# ir.net
KiCad netlist of a schematic drawn in Altium Designer
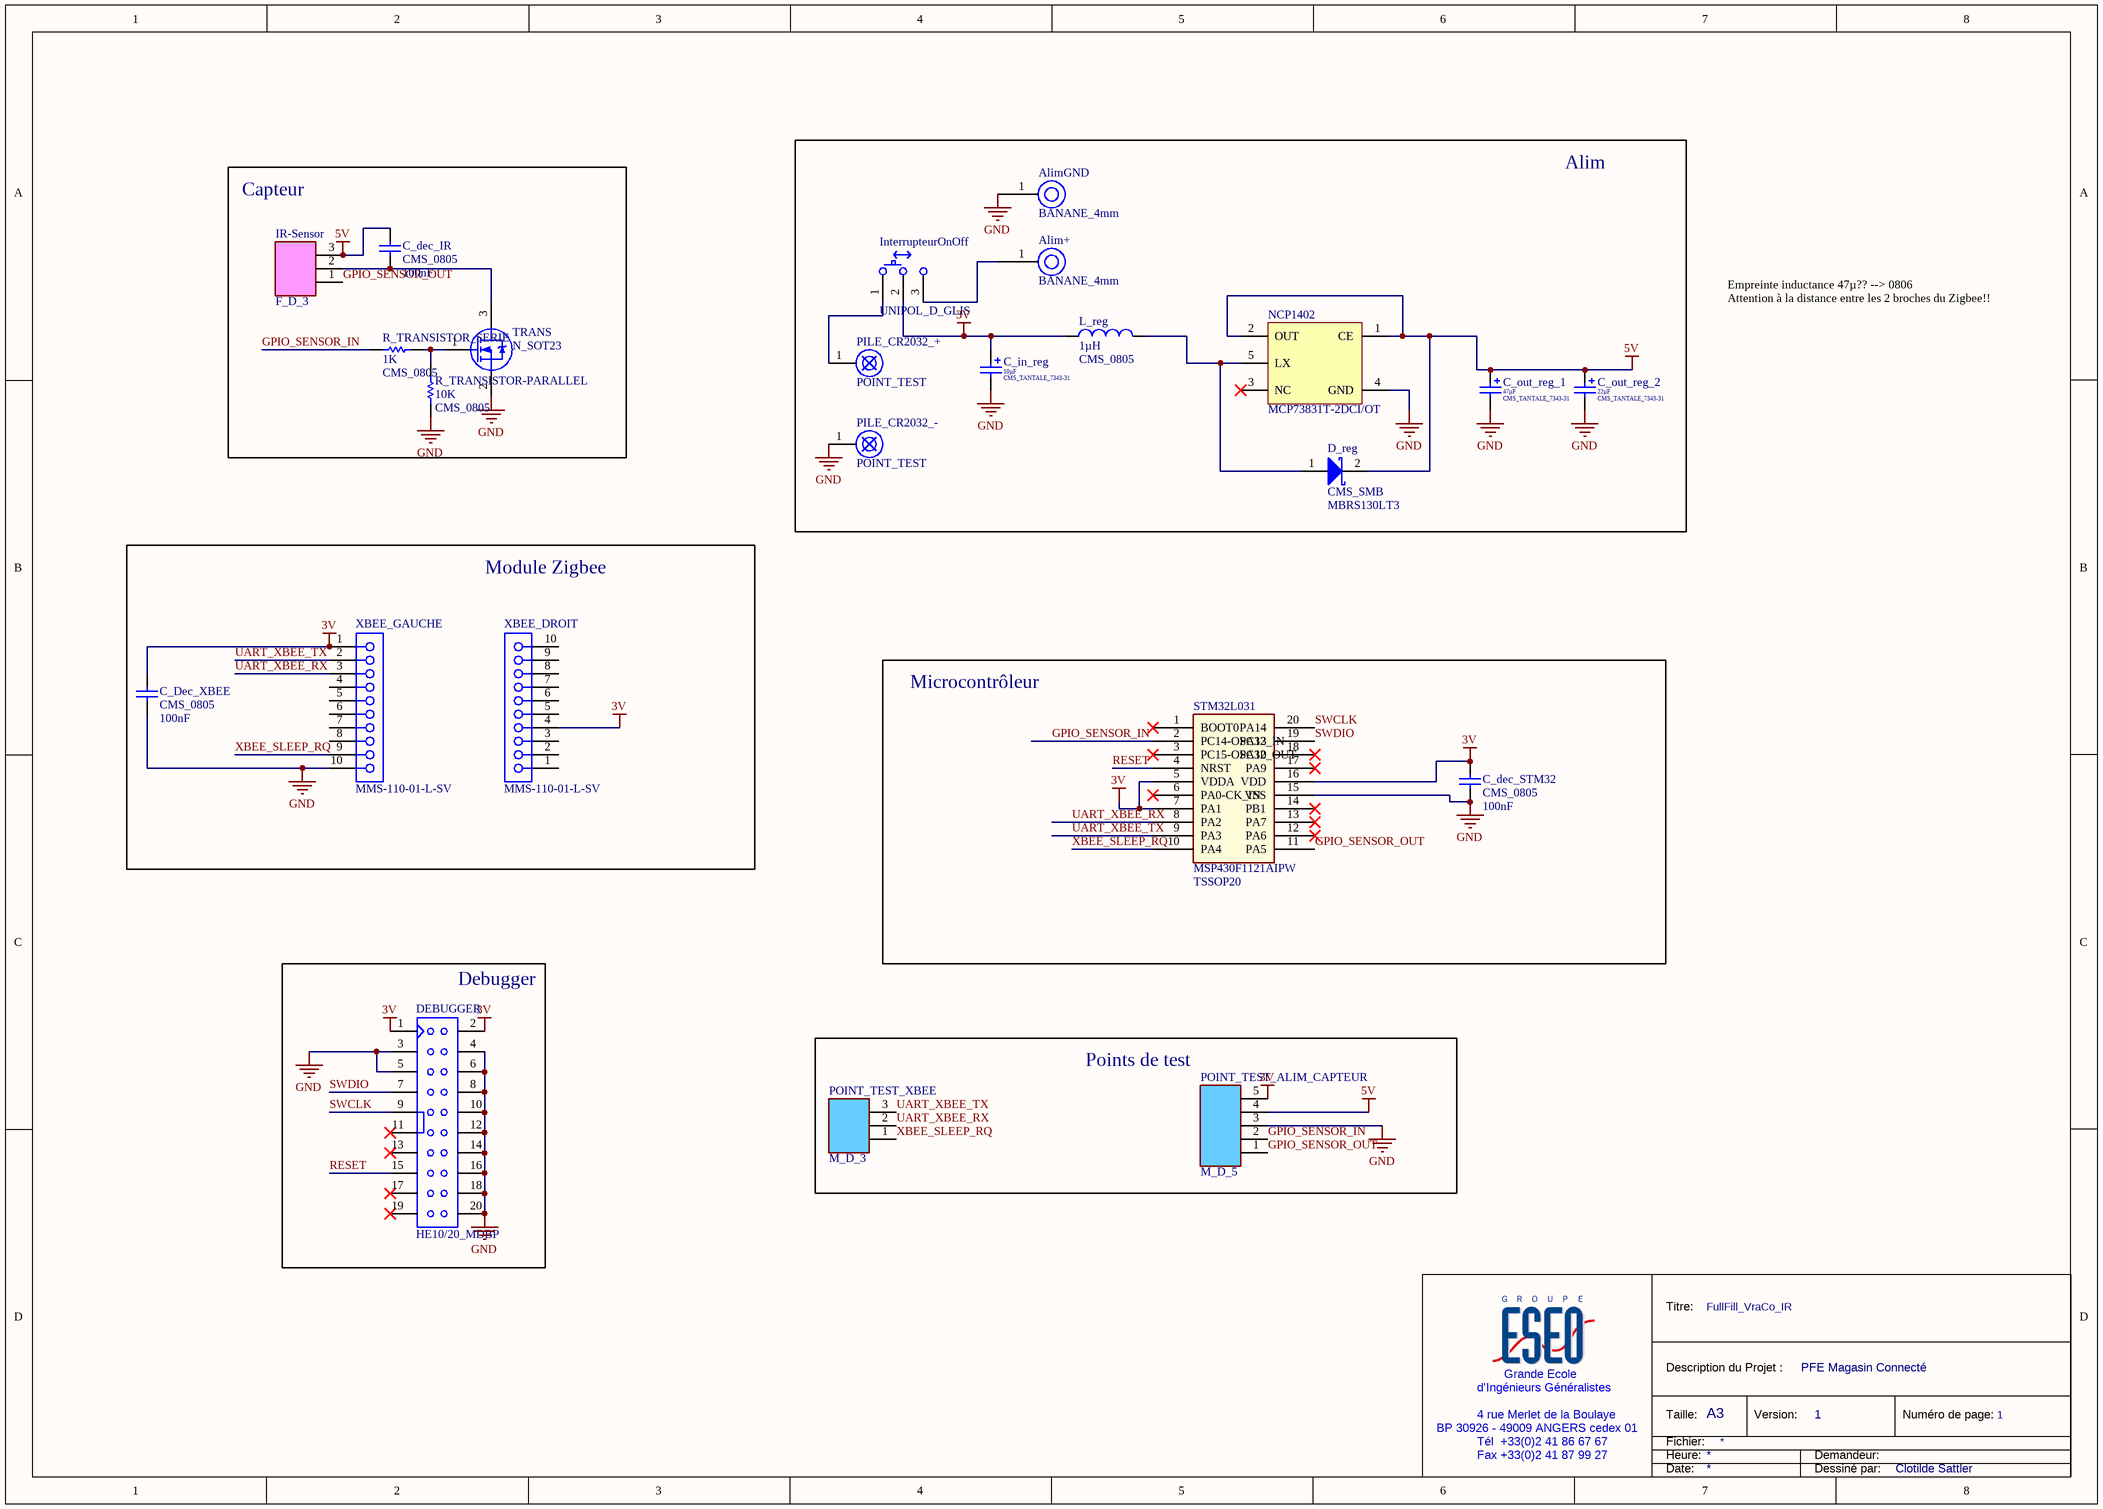
[diagram p0: ir.SchDoc]

(export (version "E")
  (design (tool "Eeschema 10.0.6"))
  (components
    (comp (ref "Alim+")
      (value "DOUILLE BANANE 4mm")
      (footprint "DOUILLE_BANANE_4mm")
      (description "DOUILLE BANANE 4 mm")
      (fields (field (name "TYPE") "BANANE_4mm"))
      (libsource (lib "connecteurs") (part "DOUILLE_BANANE_4mm"))
    )
    (comp (ref "AlimGND")
      (value "DOUILLE BANANE 4mm")
      (footprint "DOUILLE_BANANE_4mm")
      (description "DOUILLE BANANE 4 mm")
      (fields (field (name "TYPE") "BANANE_4mm"))
      (libsource (lib "connecteurs") (part "DOUILLE_BANANE_4mm"))
    )
    (comp (ref "C_dec_IR")
      (value "100nF")
      (footprint "CONDENSATEUR_CMS_0805")
      (description "CONDENSATEUR CMS CERAMIQUE 0805")
      (fields (field (name "TYPE") "CMS_0805") (field (name "Comment") "CMS_0805"))
      (libsource (lib "composants passifs") (part "CONDENSATEUR_CMS_CER_0805"))
    )
    (comp (ref "C_dec_STM32")
      (value "100nF")
      (footprint "CONDENSATEUR_CMS_0805")
      (description "CONDENSATEUR CMS CERAMIQUE 0805")
      (fields (field (name "TYPE") "CMS_0805") (field (name "Comment") "CMS_0805"))
      (libsource (lib "composants passifs") (part "CONDENSATEUR_CMS_CER_0805"))
    )
    (comp (ref "C_Dec_XBEE")
      (value "100nF")
      (footprint "CONDENSATEUR_CMS_0805")
      (description "CONDENSATEUR CMS CERAMIQUE 0805")
      (fields (field (name "TYPE") "CMS_0805") (field (name "Comment") "CMS_0805"))
      (libsource (lib "composants passifs") (part "CONDENSATEUR_CMS_CER_0805"))
    )
    (comp (ref "C_in_reg")
      (value "10µF")
      (footprint "CONDENSATEUR_CMS_POLARISE_TANTALE_D/7343-31")
      (description "CONDENSATEUR CMS POLARISE TANTALE BOITIER D/7343-31")
      (fields
        (field (name "TYPE") "CMS_TANTALE_7343-31")
        (field (name "Comment") "CMS_POLARISE_TANTALE_7343-31")
      )
      (libsource (lib "composants passifs") (part "CONDENSATEUR_CMS_POL_TANT_D_7343-31"))
    )
    (comp (ref "C_out_reg_1")
      (value "47µF")
      (footprint "CONDENSATEUR_CMS_POLARISE_TANTALE_D/7343-31")
      (description "CONDENSATEUR CMS POLARISE TANTALE BOITIER D/7343-31")
      (fields
        (field (name "TYPE") "CMS_TANTALE_7343-31")
        (field (name "Comment") "CMS_POLARISE_TANTALE_7343-31")
      )
      (libsource (lib "composants passifs") (part "CONDENSATEUR_CMS_POL_TANT_D_7343-31"))
    )
    (comp (ref "C_out_reg_2")
      (value "22µF")
      (footprint "CONDENSATEUR_CMS_POLARISE_TANTALE_D/7343-31")
      (description "CONDENSATEUR CMS POLARISE TANTALE BOITIER D/7343-31")
      (fields
        (field (name "TYPE") "CMS_TANTALE_7343-31")
        (field (name "Comment") "CMS_POLARISE_TANTALE_7343-31")
      )
      (libsource (lib "composants passifs") (part "CONDENSATEUR_CMS_POL_TANT_D_7343-31"))
    )
    (comp (ref "DEBUGGER")
      (value "HE10/20_MALE_DROIT_BAS_PROFIL")
      (footprint "HE10/20_M_D_BP")
      (description "EMBASE HE10/20 MALE DROIT BAS PROFIL")
      (fields (field (name "TYPE") "HE10/20_MDBP"))
      (libsource (lib "connecteurs") (part "HE10/20_MALE_DROIT_BAS_PROFIL"))
    )
    (comp (ref "D_reg")
      (value "DIODE_CMS_SCHOTTKY_SMB : MBRS130LT3")
      (footprint "DIODE_CMS_SMB")
      (description "DIODE CMS SCHOTTKY SMB : MBRS130LT3")
      (fields (field (name "PACKAGE") "CMS_SMB") (field (name "TYPE") "MBRS130LT3"))
      (libsource (lib "composants actifs") (part "DIODE_CMS_SCHOTTKY_SMB {colon} MBRS130LT3"))
    )
    (comp (ref "InterrupteurOnOff")
      (value "INTERRUPTEUR_UNIPOLAIRE_DROIT_GLISSIERE")
      (footprint "INTER_UNIPOL_DROIT_GLISS")
      (description "INTERRUPTEUR UNIPOLAIRE DROIT A GLISSIERE")
      (fields (field (name "TYPE") "UNIPOL_D_GLIS"))
      (libsource (lib "commutation") (part "INTERRUPTEUR_UNIPOLAIRE_DROIT_GLISSIERE"))
    )
    (comp (ref "IR-Sensor")
      (value "BARRETTE 3 CONTACTS 1 RANGEE FEMELLE DROITE")
      (footprint "BARRETTE_3_F_D")
      (fields (field (name "TYPE") "F_D_3"))
      (libsource (lib "connecteurs") (part "BARRETTE_3 CONTACTS_1 RANGEE_FEMELLE_DROITE"))
    )
    (comp (ref "L_reg")
      (value "1µH")
      (footprint "INDUCTANCE_CMS_0805")
      (description "INDUCTANCE CMS 0805")
      (fields (field (name "TYPE") "CMS_0805") (field (name "Comment") "INDUCTANCE_CMS_0805"))
      (libsource (lib "composants passifs") (part "INDUCTANCE_CMS_0805"))
    )
    (comp (ref "NCP1402")
      (value "MCP73831T-2DCI/OT")
      (footprint "SOT-23-OT5_N")
      (fields (field (name "MANUFACTURER") "Microchip"))
      (libsource (lib "energie") (part "MCP73831T-2DCI/OT"))
    )
    (comp (ref "PILE_CR2032_+")
      (value "POINT_TEST")
      (footprint "POINT_TEST")
      (description "POINT TEST")
      (libsource (lib "connecteurs") (part "POINT_TEST"))
    )
    (comp (ref "PILE_CR2032_-")
      (value "POINT_TEST")
      (footprint "POINT_TEST")
      (description "POINT TEST")
      (libsource (lib "connecteurs") (part "POINT_TEST"))
    )
    (comp (ref "POINT_TEST_ALIM_CAPTEUR")
      (value "BARRETTE_5 CONTACTS_1 RANGEE_MALE_DROITE")
      (footprint "BARRETTE_5_M_D")
      (description "BARRETTE 5 CONTACTS 1 RANGEE MALE DROITE")
      (fields (field (name "TYPE") "M_D_5"))
      (libsource (lib "connecteurs") (part "BARRETTE_5 CONTACTS_1 RANGEE_MALE_DROITE"))
    )
    (comp (ref "POINT_TEST_XBEE")
      (value "BARRETTE 3 CONTACTS 1 RANGEE MALE DROITE")
      (footprint "BARRETTE_3_M_D")
      (fields (field (name "TYPE") "M_D_3"))
      (libsource (lib "connecteurs") (part "BARRETTE_3 CONTACTS_1 RANGEE_MALE_DROITE"))
    )
    (comp (ref "R_TRANSISTOR-PARALLEL")
      (value "10K")
      (footprint "RESISTANCE_CMS_0805")
      (description "RESISTANCE CMS 0805")
      (fields (field (name "TYPE") "CMS_0805") (field (name "Comment") "RESISTANCE_CMS_0805"))
      (libsource (lib "composants passifs") (part "RESISTANCE_CMS_0805"))
    )
    (comp (ref "R_TRANSISTOR_SERIE")
      (value "1K")
      (footprint "RESISTANCE_CMS_0805")
      (description "RESISTANCE CMS 0805")
      (fields (field (name "TYPE") "CMS_0805") (field (name "Comment") "RESISTANCE_CMS_0805"))
      (libsource (lib "composants passifs") (part "RESISTANCE_CMS_0805"))
    )
    (comp (ref "STM32L031")
      (value "MSP430F1121AIPW_TSSOP20")
      (footprint "TSSOP20_PAS=0.65_LARG=6.4_LONG=6.5")
      (description "MICROCONTROLEUR FLASH - 16BITS - TSSOP20")
      (fields (field (name "TYPE") "MSP430F1121AIPW") (field (name "PACKAGE") "TSSOP20"))
      (libsource (lib "circuits integres") (part "MSP430F1121AIPW_TSSOP20"))
    )
    (comp (ref "TRANS")
      (value "TRANSISTOR_MOSFET-N_SOT23_GSD")
      (footprint "TRANSISTOR_MOSFET-N_SOT23_GSD")
      (description "TRANSISTOR MOSFET CANAL N BOITIER SOT23_GSD")
      (fields (field (name "PACKAGE") "N_SOT23"))
      (libsource (lib "composants actifs") (part "TRANSISTOR_MOSFET-N_SOT23_GSD"))
    )
    (comp (ref "XBEE_DROIT")
      (value "MMS-110-01-L-SV")
      (footprint "SMTC-MMS-110-01-X-SV")
      (fields (field (name "MANUFACTURER") "Samtec"))
      (libsource (lib "Samtec_2_mm_Pitch_Socket_Strips") (part "MMS-110-01-L-SV"))
    )
    (comp (ref "XBEE_GAUCHE")
      (value "MMS-110-01-L-SV")
      (footprint "SMTC-MMS-110-01-X-SV")
      (fields (field (name "MANUFACTURER") "Samtec"))
      (libsource (lib "Samtec_2_mm_Pitch_Socket_Strips") (part "MMS-110-01-L-SV"))
    )
  )
  (nets
    (net (code "1") (name "/GPIO_SENSOR_IN") (class "Default")
      (node (ref "POINT_TEST_ALIM_CAPTEUR") (pin "2") (pinfunction "2_2") (pintype "passive"))
      (node (ref "R_TRANSISTOR_SERIE") (pin "1") (pinfunction "1_1") (pintype "passive"))
      (node (ref "STM32L031") (pin "2") (pinfunction "PC14-OSC32_IN_2") (pintype "passive"))
    )
    (net (code "2") (name "/GPIO_SENSOR_OUT") (class "Default")
      (node (ref "IR-Sensor") (pin "1") (pinfunction "GND_1") (pintype "passive"))
      (node (ref "POINT_TEST_ALIM_CAPTEUR") (pin "1") (pinfunction "1_1") (pintype "passive"))
      (node (ref "STM32L031") (pin "11") (pinfunction "PA5_11") (pintype "passive"))
    )
    (net (code "3") (name "/RESET") (class "Default")
      (node (ref "DEBUGGER") (pin "15") (pinfunction "15_15") (pintype "passive"))
      (node (ref "STM32L031") (pin "4") (pinfunction "NRST_4") (pintype "passive"))
    )
    (net (code "4") (name "/SWCLK") (class "Default")
      (node (ref "DEBUGGER") (pin "9") (pinfunction "9_9") (pintype "passive"))
      (node (ref "STM32L031") (pin "20") (pinfunction "PA14_20") (pintype "passive"))
    )
    (net (code "5") (name "/SWDIO") (class "Default")
      (node (ref "DEBUGGER") (pin "7") (pinfunction "7_7") (pintype "passive"))
      (node (ref "STM32L031") (pin "19") (pinfunction "PA13_19") (pintype "passive"))
    )
    (net (code "6") (name "/UART_XBEE_RX") (class "Default")
      (node (ref "POINT_TEST_XBEE") (pin "2") (pinfunction "2_2") (pintype "passive"))
      (node (ref "STM32L031") (pin "8") (pinfunction "PA2_8") (pintype "passive"))
      (node (ref "XBEE_GAUCHE") (pin "3") (pinfunction "3_3") (pintype "passive"))
    )
    (net (code "7") (name "/UART_XBEE_TX") (class "Default")
      (node (ref "POINT_TEST_XBEE") (pin "3") (pinfunction "3_3") (pintype "passive"))
      (node (ref "STM32L031") (pin "9") (pinfunction "PA3_9") (pintype "passive"))
      (node (ref "XBEE_GAUCHE") (pin "2") (pinfunction "2_2") (pintype "passive"))
    )
    (net (code "8") (name "/XBEE_SLEEP_RQ") (class "Default")
      (node (ref "POINT_TEST_XBEE") (pin "1") (pinfunction "1_1") (pintype "passive"))
      (node (ref "STM32L031") (pin "10") (pinfunction "PA4_10") (pintype "passive"))
      (node (ref "XBEE_GAUCHE") (pin "9") (pinfunction "9_9") (pintype "passive"))
    )
    (net (code "9") (name "3V") (class "Default")
      (node (ref "C_Dec_XBEE") (pin "2") (pinfunction "2_2") (pintype "passive"))
      (node (ref "C_dec_STM32") (pin "2") (pinfunction "2_2") (pintype "passive"))
      (node (ref "C_in_reg") (pin "1") (pinfunction "1_1") (pintype "passive"))
      (node (ref "DEBUGGER") (pin "1") (pinfunction "1_1") (pintype "passive"))
      (node (ref "DEBUGGER") (pin "2") (pinfunction "2_2") (pintype "passive"))
      (node (ref "InterrupteurOnOff") (pin "2") (pinfunction "2_2") (pintype "passive"))
      (node (ref "L_reg") (pin "1") (pinfunction "1_1") (pintype "passive"))
      (node (ref "POINT_TEST_ALIM_CAPTEUR") (pin "5") (pinfunction "5_5") (pintype "passive"))
      (node (ref "STM32L031") (pin "16") (pinfunction "VDD_16") (pintype "passive"))
      (node (ref "STM32L031") (pin "5") (pinfunction "VDDA_5") (pintype "passive"))
      (node (ref "STM32L031") (pin "7") (pinfunction "PA1_7") (pintype "passive"))
      (node (ref "XBEE_DROIT") (pin "4") (pinfunction "4_4") (pintype "passive"))
      (node (ref "XBEE_GAUCHE") (pin "1") (pinfunction "1_1") (pintype "passive"))
    )
    (net (code "10") (name "5V") (class "Default")
      (node (ref "C_dec_IR") (pin "2") (pinfunction "2_2") (pintype "passive"))
      (node (ref "C_out_reg_1") (pin "1") (pinfunction "1_1") (pintype "passive"))
      (node (ref "C_out_reg_2") (pin "1") (pinfunction "1_1") (pintype "passive"))
      (node (ref "D_reg") (pin "2") (pinfunction "2_2") (pintype "passive"))
      (node (ref "IR-Sensor") (pin "3") (pinfunction "OUT_3") (pintype "passive"))
      (node (ref "NCP1402") (pin "1") (pinfunction "CE_1") (pintype "passive"))
      (node (ref "NCP1402") (pin "2") (pinfunction "OUT_2") (pintype "passive"))
      (node (ref "POINT_TEST_ALIM_CAPTEUR") (pin "4") (pinfunction "4_4") (pintype "passive"))
    )
    (net (code "11") (name "GND") (class "Default")
      (node (ref "AlimGND") (pin "1") (pinfunction "1_1") (pintype "passive"))
      (node (ref "C_Dec_XBEE") (pin "1") (pinfunction "1_1") (pintype "passive"))
      (node (ref "C_dec_STM32") (pin "1") (pinfunction "1_1") (pintype "passive"))
      (node (ref "C_in_reg") (pin "2") (pinfunction "2_2") (pintype "passive"))
      (node (ref "C_out_reg_1") (pin "2") (pinfunction "2_2") (pintype "passive"))
      (node (ref "C_out_reg_2") (pin "2") (pinfunction "2_2") (pintype "passive"))
      (node (ref "DEBUGGER") (pin "10") (pinfunction "10_10") (pintype "passive"))
      (node (ref "DEBUGGER") (pin "12") (pinfunction "12_12") (pintype "passive"))
      (node (ref "DEBUGGER") (pin "14") (pinfunction "14_14") (pintype "passive"))
      (node (ref "DEBUGGER") (pin "16") (pinfunction "16_16") (pintype "passive"))
      (node (ref "DEBUGGER") (pin "18") (pinfunction "18_18") (pintype "passive"))
      (node (ref "DEBUGGER") (pin "20") (pinfunction "20_20") (pintype "passive"))
      (node (ref "DEBUGGER") (pin "3") (pinfunction "3_3") (pintype "passive"))
      (node (ref "DEBUGGER") (pin "4") (pinfunction "4_4") (pintype "passive"))
      (node (ref "DEBUGGER") (pin "5") (pinfunction "5_5") (pintype "passive"))
      (node (ref "DEBUGGER") (pin "6") (pinfunction "6_6") (pintype "passive"))
      (node (ref "DEBUGGER") (pin "8") (pinfunction "8_8") (pintype "passive"))
      (node (ref "NCP1402") (pin "4") (pinfunction "GND_4") (pintype "power_in"))
      (node (ref "PILE_CR2032_-") (pin "1") (pinfunction "3_1") (pintype "passive"))
      (node (ref "POINT_TEST_ALIM_CAPTEUR") (pin "3") (pinfunction "3_3") (pintype "passive"))
      (node (ref "R_TRANSISTOR-PARALLEL") (pin "1") (pinfunction "1_1") (pintype "passive"))
      (node (ref "STM32L031") (pin "15") (pinfunction "VSS_15") (pintype "passive"))
      (node (ref "TRANS") (pin "2") (pinfunction "S_2") (pintype "passive"))
      (node (ref "XBEE_GAUCHE") (pin "10") (pinfunction "10_10") (pintype "passive"))
    )
    (net (code "12") (name "Net-(Alim+-Pad1)") (class "Default")
      (node (ref "Alim+") (pin "1") (pinfunction "1_1") (pintype "passive"))
      (node (ref "InterrupteurOnOff") (pin "3") (pinfunction "3_3") (pintype "passive"))
    )
    (net (code "13") (name "Net-(IR-Sensor-VCC)") (class "Default")
      (node (ref "C_dec_IR") (pin "1") (pinfunction "1_1") (pintype "passive"))
      (node (ref "IR-Sensor") (pin "2") (pinfunction "VCC_2") (pintype "passive"))
      (node (ref "TRANS") (pin "3") (pinfunction "D_3") (pintype "passive"))
    )
    (net (code "14") (name "Net-(NCP1402-LX)") (class "Default")
      (node (ref "D_reg") (pin "1") (pinfunction "1_1") (pintype "passive"))
      (node (ref "L_reg") (pin "2") (pinfunction "2_2") (pintype "passive"))
      (node (ref "NCP1402") (pin "5") (pinfunction "LX_5") (pintype "passive"))
    )
    (net (code "15") (name "Net-(PILE_CR2032_+-3)") (class "Default")
      (node (ref "InterrupteurOnOff") (pin "1") (pinfunction "1_1") (pintype "passive"))
      (node (ref "PILE_CR2032_+") (pin "1") (pinfunction "3_1") (pintype "passive"))
    )
    (net (code "16") (name "Net-(TRANS-G)") (class "Default")
      (node (ref "R_TRANSISTOR-PARALLEL") (pin "2") (pinfunction "2_2") (pintype "passive"))
      (node (ref "R_TRANSISTOR_SERIE") (pin "2") (pinfunction "2_2") (pintype "passive"))
      (node (ref "TRANS") (pin "1") (pinfunction "G_1") (pintype "passive"))
    )
    (net (code "17") (name "unconnected-(DEBUGGER-Pad11)") (class "Default")
      (node (ref "DEBUGGER") (pin "11") (pinfunction "11_11") (pintype "passive+no_connect"))
    )
    (net (code "18") (name "unconnected-(DEBUGGER-Pad13)") (class "Default")
      (node (ref "DEBUGGER") (pin "13") (pinfunction "13_13") (pintype "passive+no_connect"))
    )
    (net (code "19") (name "unconnected-(DEBUGGER-Pad17)") (class "Default")
      (node (ref "DEBUGGER") (pin "17") (pinfunction "17_17") (pintype "passive+no_connect"))
    )
    (net (code "20") (name "unconnected-(DEBUGGER-Pad19)") (class "Default")
      (node (ref "DEBUGGER") (pin "19") (pinfunction "19_19") (pintype "passive+no_connect"))
    )
    (net (code "21") (name "unconnected-(NCP1402-NC-Pad3)") (class "Default")
      (node (ref "NCP1402") (pin "3") (pinfunction "NC_3") (pintype "passive+no_connect"))
    )
    (net (code "22") (name "unconnected-(STM32L031-BOOT0-Pad1)") (class "Default")
      (node (ref "STM32L031") (pin "1") (pinfunction "BOOT0_1") (pintype "passive+no_connect"))
    )
    (net (code "23") (name "unconnected-(STM32L031-PA0-CK_IN-Pad6)") (class "Default")
      (node (ref "STM32L031") (pin "6") (pinfunction "PA0-CK_IN_6") (pintype "passive+no_connect"))
    )
    (net (code "24") (name "unconnected-(STM32L031-PA6-Pad12)") (class "Default")
      (node (ref "STM32L031") (pin "12") (pinfunction "PA6_12") (pintype "passive+no_connect"))
    )
    (net (code "25") (name "unconnected-(STM32L031-PA7-Pad13)") (class "Default")
      (node (ref "STM32L031") (pin "13") (pinfunction "PA7_13") (pintype "passive+no_connect"))
    )
    (net (code "26") (name "unconnected-(STM32L031-PA9-Pad17)") (class "Default")
      (node (ref "STM32L031") (pin "17") (pinfunction "PA9_17") (pintype "passive+no_connect"))
    )
    (net (code "27") (name "unconnected-(STM32L031-PA10-Pad18)") (class "Default")
      (node (ref "STM32L031") (pin "18") (pinfunction "PA10_18") (pintype "passive+no_connect"))
    )
    (net (code "28") (name "unconnected-(STM32L031-PB1-Pad14)") (class "Default")
      (node (ref "STM32L031") (pin "14") (pinfunction "PB1_14") (pintype "passive+no_connect"))
    )
    (net (code "29") (name "unconnected-(STM32L031-PC15-OSC32_OUT-Pad3)") (class "Default")
      (node (ref "STM32L031") (pin "3") (pinfunction "PC15-OSC32_OUT_3") (pintype "passive+no_connect"))
    )
    (net (code "30") (name "unconnected-(XBEE_DROIT-Pad1)") (class "Default")
      (node (ref "XBEE_DROIT") (pin "1") (pinfunction "1_1") (pintype "passive"))
    )
    (net (code "31") (name "unconnected-(XBEE_DROIT-Pad2)") (class "Default")
      (node (ref "XBEE_DROIT") (pin "2") (pinfunction "2_2") (pintype "passive"))
    )
    (net (code "32") (name "unconnected-(XBEE_DROIT-Pad3)") (class "Default")
      (node (ref "XBEE_DROIT") (pin "3") (pinfunction "3_3") (pintype "passive"))
    )
    (net (code "33") (name "unconnected-(XBEE_DROIT-Pad5)") (class "Default")
      (node (ref "XBEE_DROIT") (pin "5") (pinfunction "5_5") (pintype "passive"))
    )
    (net (code "34") (name "unconnected-(XBEE_DROIT-Pad6)") (class "Default")
      (node (ref "XBEE_DROIT") (pin "6") (pinfunction "6_6") (pintype "passive"))
    )
    (net (code "35") (name "unconnected-(XBEE_DROIT-Pad7)") (class "Default")
      (node (ref "XBEE_DROIT") (pin "7") (pinfunction "7_7") (pintype "passive"))
    )
    (net (code "36") (name "unconnected-(XBEE_DROIT-Pad8)") (class "Default")
      (node (ref "XBEE_DROIT") (pin "8") (pinfunction "8_8") (pintype "passive"))
    )
    (net (code "37") (name "unconnected-(XBEE_DROIT-Pad9)") (class "Default")
      (node (ref "XBEE_DROIT") (pin "9") (pinfunction "9_9") (pintype "passive"))
    )
    (net (code "38") (name "unconnected-(XBEE_DROIT-Pad10)") (class "Default")
      (node (ref "XBEE_DROIT") (pin "10") (pinfunction "10_10") (pintype "passive"))
    )
    (net (code "39") (name "unconnected-(XBEE_GAUCHE-Pad4)") (class "Default")
      (node (ref "XBEE_GAUCHE") (pin "4") (pinfunction "4_4") (pintype "passive"))
    )
    (net (code "40") (name "unconnected-(XBEE_GAUCHE-Pad5)") (class "Default")
      (node (ref "XBEE_GAUCHE") (pin "5") (pinfunction "5_5") (pintype "passive"))
    )
    (net (code "41") (name "unconnected-(XBEE_GAUCHE-Pad6)") (class "Default")
      (node (ref "XBEE_GAUCHE") (pin "6") (pinfunction "6_6") (pintype "passive"))
    )
    (net (code "42") (name "unconnected-(XBEE_GAUCHE-Pad7)") (class "Default")
      (node (ref "XBEE_GAUCHE") (pin "7") (pinfunction "7_7") (pintype "passive"))
    )
    (net (code "43") (name "unconnected-(XBEE_GAUCHE-Pad8)") (class "Default")
      (node (ref "XBEE_GAUCHE") (pin "8") (pinfunction "8_8") (pintype "passive"))
    )
  )
)
